# MODUL_PORTEXP_V101.net
KiCad netlist of a schematic drawn in EAGLE
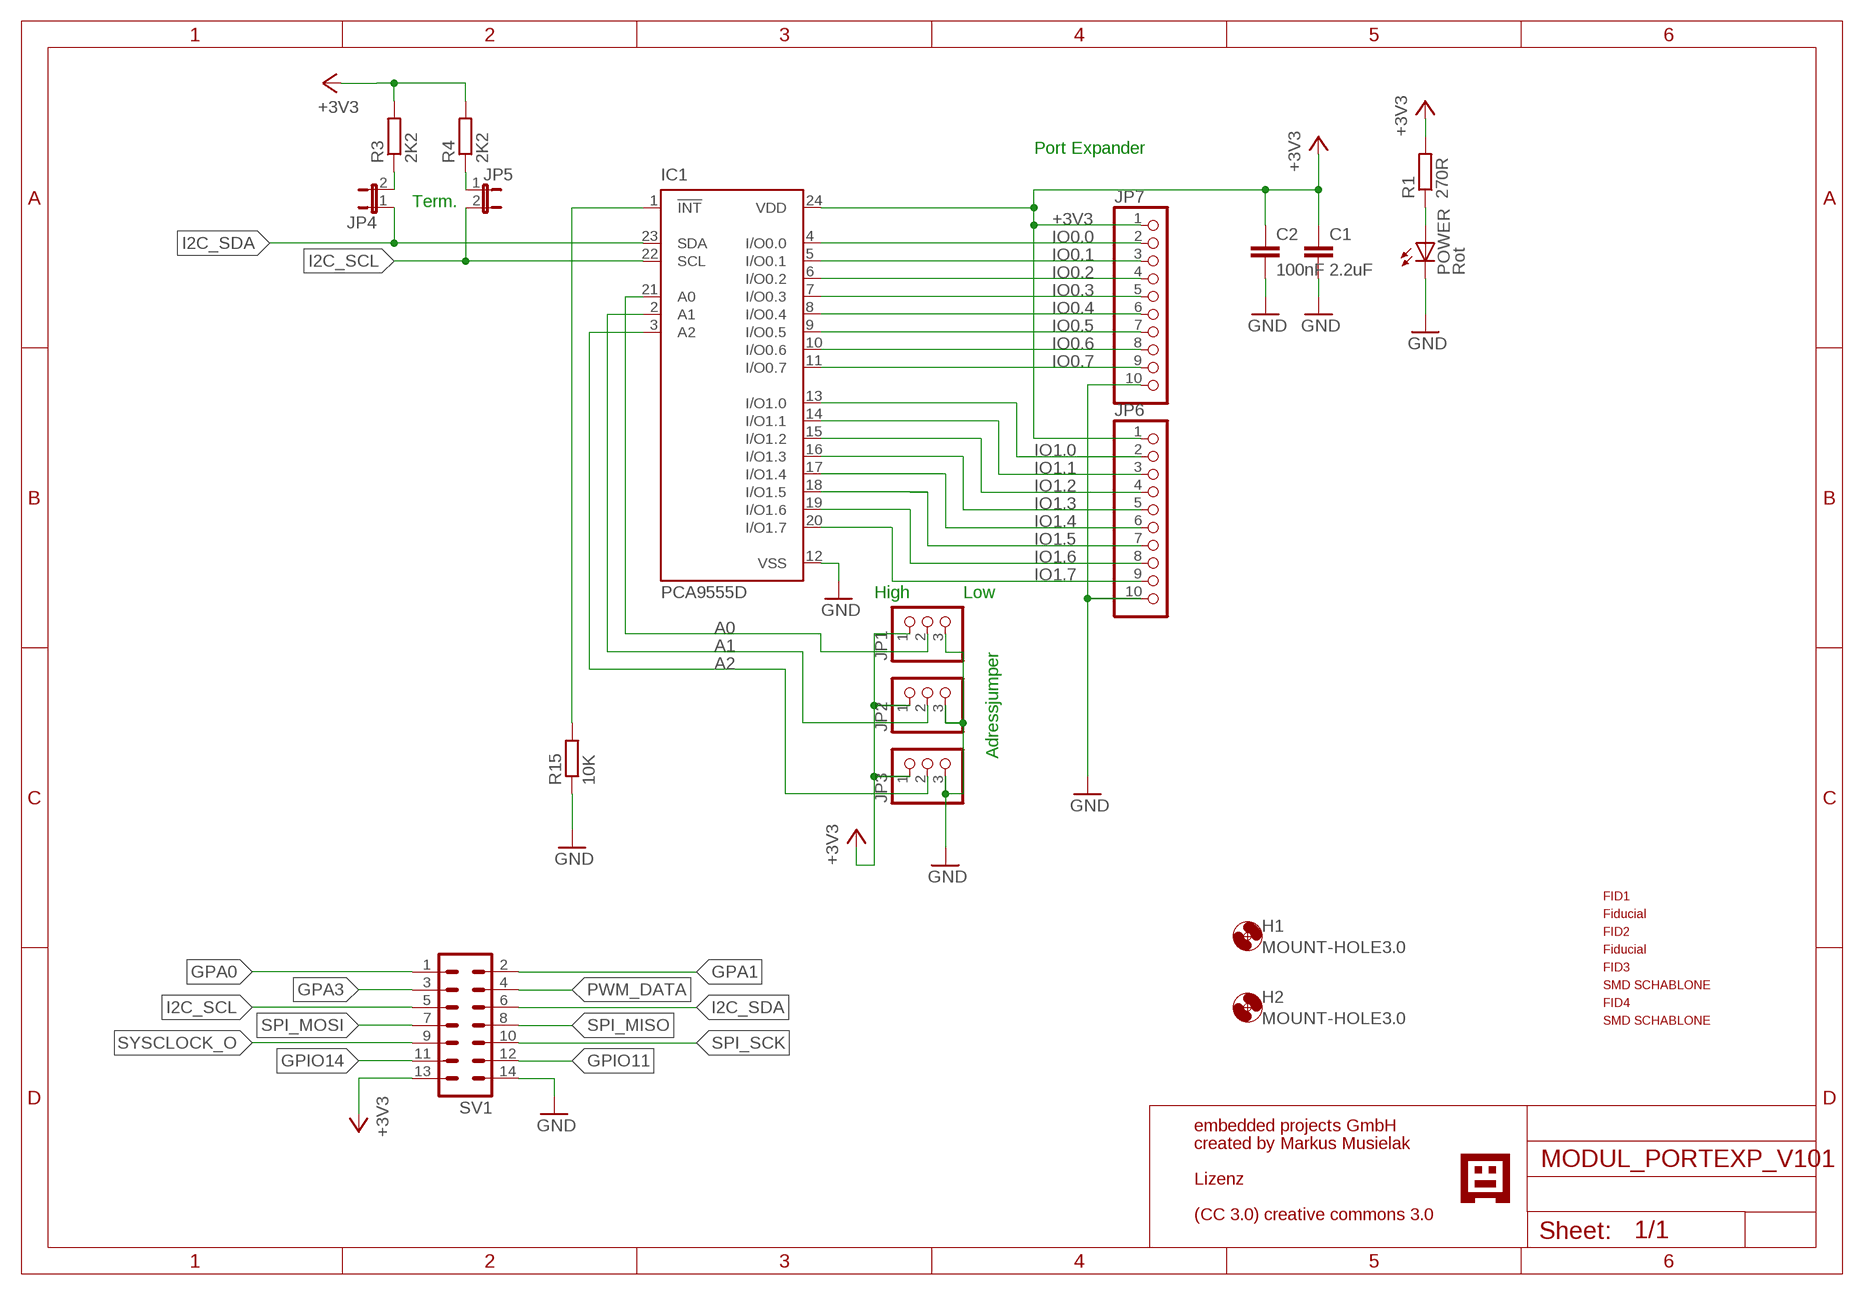
[diagram p0: schematic, sheet 1]

(export (version "E")
  (design (tool "Eeschema 10.0.6"))
  (components
    (comp (ref "C1")
      (value "2.2uF")
      (footprint "eagle-import:C0805")
      (libsource (lib "eagle-import") (part "C-EUC0805"))
    )
    (comp (ref "C2")
      (value "100nF")
      (footprint "eagle-import:C0805")
      (libsource (lib "eagle-import") (part "C-EUC0805"))
    )
    (comp (ref "FID1")
      (value "PASSERMARKEN_FIDUCIAL")
      (footprint "eagle-import:PASSERMARKEN_FIDUCIAL")
      (libsource (lib "eagle-import") (part "PASSERMARKEN_FIDUCIAL"))
    )
    (comp (ref "FID2")
      (value "PASSERMARKEN_FIDUCIAL")
      (footprint "eagle-import:PASSERMARKEN_FIDUCIAL")
      (libsource (lib "eagle-import") (part "PASSERMARKEN_FIDUCIAL"))
    )
    (comp (ref "FID3")
      (value "PASSERMARKEN_FIDUCIAL")
      (footprint "eagle-import:PASSERMARKEN_FIDUCIAL")
      (libsource (lib "eagle-import") (part "SMDSCHABLONE_PASSERMARKEN_FIDUCIAL"))
    )
    (comp (ref "FID4")
      (value "PASSERMARKEN_FIDUCIAL")
      (footprint "eagle-import:PASSERMARKEN_FIDUCIAL")
      (libsource (lib "eagle-import") (part "SMDSCHABLONE_PASSERMARKEN_FIDUCIAL"))
    )
    (comp (ref "H1")
      (value "MOUNT-HOLE3.0")
      (footprint "eagle-import:3,0")
      (libsource (lib "eagle-import") (part "MOUNT-HOLE3.0"))
    )
    (comp (ref "H2")
      (value "MOUNT-HOLE3.0")
      (footprint "eagle-import:3,0")
      (libsource (lib "eagle-import") (part "MOUNT-HOLE3.0"))
    )
    (comp (ref "IC1")
      (value "PCA9555D")
      (footprint "eagle-import:SO24")
      (fields (field (name "MPN") "PCA9555DW") (field (name "OC_FARNELL") "8906076"))
      (libsource (lib "eagle-import") (part "PCA9555D"))
    )
    (comp (ref "JP1")
      (value "PINHD-1X3")
      (footprint "eagle-import:1X03")
      (libsource (lib "eagle-import") (part "PINHD-1X3"))
    )
    (comp (ref "JP2")
      (value "PINHD-1X3")
      (footprint "eagle-import:1X03")
      (libsource (lib "eagle-import") (part "PINHD-1X3"))
    )
    (comp (ref "JP3")
      (value "PINHD-1X3")
      (footprint "eagle-import:1X03")
      (libsource (lib "eagle-import") (part "PINHD-1X3"))
    )
    (comp (ref "JP4")
      (value "JP1E")
      (footprint "eagle-import:JP1")
      (libsource (lib "eagle-import") (part "JP1E"))
    )
    (comp (ref "JP5")
      (value "JP1E")
      (footprint "eagle-import:JP1")
      (libsource (lib "eagle-import") (part "JP1E"))
    )
    (comp (ref "JP6")
      (value "PINHD-1X10")
      (footprint "eagle-import:1X10")
      (libsource (lib "eagle-import") (part "PINHD-1X10"))
    )
    (comp (ref "JP7")
      (value "PINHD-1X10")
      (footprint "eagle-import:1X10")
      (libsource (lib "eagle-import") (part "PINHD-1X10"))
    )
    (comp (ref "POWER")
      (value "Rot")
      (footprint "eagle-import:CHIP-LED0805")
      (libsource (lib "eagle-import") (part "LEDCHIP-LED0805"))
    )
    (comp (ref "R1")
      (value "270R")
      (footprint "eagle-import:R0805")
      (libsource (lib "eagle-import") (part "R-EU_R0805"))
    )
    (comp (ref "R3")
      (value "2K2")
      (footprint "eagle-import:R0805")
      (libsource (lib "eagle-import") (part "R-EU_R0805"))
    )
    (comp (ref "R4")
      (value "2K2")
      (footprint "eagle-import:R0805")
      (libsource (lib "eagle-import") (part "R-EU_R0805"))
    )
    (comp (ref "R15")
      (value "10K")
      (footprint "eagle-import:R0805")
      (libsource (lib "eagle-import") (part "R-EU_R0805"))
    )
    (comp (ref "SV1")
      (value "ML14")
      (footprint "eagle-import:ML14")
      (libsource (lib "eagle-import") (part "ML14"))
    )
    (comp (ref "U$2")
      (value "GNUBLINLOGOSIEB")
      (footprint "eagle-import:GNUSIEBDRUCK")
      (libsource (lib "eagle-import") (part "GNUBLINLOGOSIEB"))
    )
  )
  (nets
    (net (code "1") (name "+3V3") (class "Default")
      (node (ref "C1") (pin "1") (pinfunction "1_1") (pintype "passive"))
      (node (ref "C2") (pin "1") (pinfunction "1_1") (pintype "passive"))
      (node (ref "IC1") (pin "24") (pinfunction "VDD_24") (pintype "power_in"))
      (node (ref "JP1") (pin "1") (pinfunction "1_1") (pintype "passive"))
      (node (ref "JP2") (pin "1") (pinfunction "1_1") (pintype "passive"))
      (node (ref "JP3") (pin "1") (pinfunction "1_1") (pintype "passive"))
      (node (ref "JP6") (pin "1") (pinfunction "1_1") (pintype "passive"))
      (node (ref "JP7") (pin "1") (pinfunction "1_1") (pintype "passive"))
      (node (ref "R1") (pin "2") (pinfunction "2_2") (pintype "passive"))
      (node (ref "R3") (pin "2") (pinfunction "2_2") (pintype "passive"))
      (node (ref "R4") (pin "2") (pinfunction "2_2") (pintype "passive"))
      (node (ref "SV1") (pin "13") (pinfunction "13_13") (pintype "passive"))
    )
    (net (code "2") (name "/A0") (class "Default")
      (node (ref "IC1") (pin "21") (pinfunction "A0_21") (pintype "input"))
      (node (ref "JP1") (pin "2") (pinfunction "2_2") (pintype "passive"))
    )
    (net (code "3") (name "/A1") (class "Default")
      (node (ref "IC1") (pin "2") (pinfunction "A1_2") (pintype "input"))
      (node (ref "JP2") (pin "2") (pinfunction "2_2") (pintype "passive"))
    )
    (net (code "4") (name "/A2") (class "Default")
      (node (ref "IC1") (pin "3") (pinfunction "A2_3") (pintype "input"))
      (node (ref "JP3") (pin "2") (pinfunction "2_2") (pintype "passive"))
    )
    (net (code "5") (name "/IO0.0") (class "Default")
      (node (ref "IC1") (pin "4") (pinfunction "I/O0.0_4") (pintype "bidirectional"))
      (node (ref "JP7") (pin "2") (pinfunction "2_2") (pintype "passive"))
    )
    (net (code "6") (name "/IO0.1") (class "Default")
      (node (ref "IC1") (pin "5") (pinfunction "I/O0.1_5") (pintype "bidirectional"))
      (node (ref "JP7") (pin "3") (pinfunction "3_3") (pintype "passive"))
    )
    (net (code "7") (name "/IO0.2") (class "Default")
      (node (ref "IC1") (pin "6") (pinfunction "I/O0.2_6") (pintype "bidirectional"))
      (node (ref "JP7") (pin "4") (pinfunction "4_4") (pintype "passive"))
    )
    (net (code "8") (name "/IO0.3") (class "Default")
      (node (ref "IC1") (pin "7") (pinfunction "I/O0.3_7") (pintype "bidirectional"))
      (node (ref "JP7") (pin "5") (pinfunction "5_5") (pintype "passive"))
    )
    (net (code "9") (name "/IO0.4") (class "Default")
      (node (ref "IC1") (pin "8") (pinfunction "I/O0.4_8") (pintype "bidirectional"))
      (node (ref "JP7") (pin "6") (pinfunction "6_6") (pintype "passive"))
    )
    (net (code "10") (name "/IO0.5") (class "Default")
      (node (ref "IC1") (pin "9") (pinfunction "I/O0.5_9") (pintype "bidirectional"))
      (node (ref "JP7") (pin "7") (pinfunction "7_7") (pintype "passive"))
    )
    (net (code "11") (name "/IO0.6") (class "Default")
      (node (ref "IC1") (pin "10") (pinfunction "I/O0.6_10") (pintype "bidirectional"))
      (node (ref "JP7") (pin "8") (pinfunction "8_8") (pintype "passive"))
    )
    (net (code "12") (name "/IO0.7") (class "Default")
      (node (ref "IC1") (pin "11") (pinfunction "I/O0.7_11") (pintype "bidirectional"))
      (node (ref "JP7") (pin "9") (pinfunction "9_9") (pintype "passive"))
    )
    (net (code "13") (name "/IO1.0") (class "Default")
      (node (ref "IC1") (pin "13") (pinfunction "I/O1.0_13") (pintype "bidirectional"))
      (node (ref "JP6") (pin "2") (pinfunction "2_2") (pintype "passive"))
    )
    (net (code "14") (name "/IO1.1") (class "Default")
      (node (ref "IC1") (pin "14") (pinfunction "I/O1.1_14") (pintype "bidirectional"))
      (node (ref "JP6") (pin "3") (pinfunction "3_3") (pintype "passive"))
    )
    (net (code "15") (name "/IO1.2") (class "Default")
      (node (ref "IC1") (pin "15") (pinfunction "I/O1.2_15") (pintype "bidirectional"))
      (node (ref "JP6") (pin "4") (pinfunction "4_4") (pintype "passive"))
    )
    (net (code "16") (name "/IO1.3") (class "Default")
      (node (ref "IC1") (pin "16") (pinfunction "I/O1.3_16") (pintype "bidirectional"))
      (node (ref "JP6") (pin "5") (pinfunction "5_5") (pintype "passive"))
    )
    (net (code "17") (name "/IO1.4") (class "Default")
      (node (ref "IC1") (pin "17") (pinfunction "I/O1.4_17") (pintype "bidirectional"))
      (node (ref "JP6") (pin "6") (pinfunction "6_6") (pintype "passive"))
    )
    (net (code "18") (name "/IO1.5") (class "Default")
      (node (ref "IC1") (pin "18") (pinfunction "I/O1.5_18") (pintype "bidirectional"))
      (node (ref "JP6") (pin "7") (pinfunction "7_7") (pintype "passive"))
    )
    (net (code "19") (name "/IO1.6") (class "Default")
      (node (ref "IC1") (pin "19") (pinfunction "I/O1.6_19") (pintype "bidirectional"))
      (node (ref "JP6") (pin "8") (pinfunction "8_8") (pintype "passive"))
    )
    (net (code "20") (name "/IO1.7") (class "Default")
      (node (ref "IC1") (pin "20") (pinfunction "I/O1.7_20") (pintype "bidirectional"))
      (node (ref "JP6") (pin "9") (pinfunction "9_9") (pintype "passive"))
    )
    (net (code "21") (name "GND") (class "Default")
      (node (ref "C1") (pin "2") (pinfunction "2_2") (pintype "passive"))
      (node (ref "C2") (pin "2") (pinfunction "2_2") (pintype "passive"))
      (node (ref "IC1") (pin "12") (pinfunction "VSS_12") (pintype "power_in"))
      (node (ref "JP1") (pin "3") (pinfunction "3_3") (pintype "passive"))
      (node (ref "JP2") (pin "3") (pinfunction "3_3") (pintype "passive"))
      (node (ref "JP3") (pin "3") (pinfunction "3_3") (pintype "passive"))
      (node (ref "JP6") (pin "10") (pinfunction "10_10") (pintype "passive"))
      (node (ref "JP7") (pin "10") (pinfunction "10_10") (pintype "passive"))
      (node (ref "POWER") (pin "C") (pinfunction "C_C") (pintype "passive"))
      (node (ref "R15") (pin "1") (pinfunction "1_1") (pintype "passive"))
      (node (ref "SV1") (pin "14") (pinfunction "14_14") (pintype "passive"))
    )
    (net (code "22") (name "GPA0") (class "Default")
      (node (ref "SV1") (pin "1") (pinfunction "1_1") (pintype "passive"))
    )
    (net (code "23") (name "GPA1") (class "Default")
      (node (ref "SV1") (pin "2") (pinfunction "2_2") (pintype "passive"))
    )
    (net (code "24") (name "GPA3") (class "Default")
      (node (ref "SV1") (pin "3") (pinfunction "3_3") (pintype "passive"))
    )
    (net (code "25") (name "GPIO11") (class "Default")
      (node (ref "SV1") (pin "12") (pinfunction "12_12") (pintype "passive"))
    )
    (net (code "26") (name "GPIO14") (class "Default")
      (node (ref "SV1") (pin "11") (pinfunction "11_11") (pintype "passive"))
    )
    (net (code "27") (name "I2C_SCL") (class "Default")
      (node (ref "IC1") (pin "22") (pinfunction "SCL_22") (pintype "input"))
      (node (ref "JP5") (pin "2") (pinfunction "2_2") (pintype "passive"))
      (node (ref "SV1") (pin "5") (pinfunction "5_5") (pintype "passive"))
    )
    (net (code "28") (name "I2C_SDA") (class "Default")
      (node (ref "IC1") (pin "23") (pinfunction "SDA_23") (pintype "bidirectional"))
      (node (ref "JP4") (pin "1") (pinfunction "1_1") (pintype "passive"))
      (node (ref "SV1") (pin "6") (pinfunction "6_6") (pintype "passive"))
    )
    (net (code "29") (name "Net-(IC1-~{INT})") (class "Default")
      (node (ref "IC1") (pin "1") (pinfunction "~{INT}_1") (pintype "output"))
      (node (ref "R15") (pin "2") (pinfunction "2_2") (pintype "passive"))
    )
    (net (code "30") (name "Net-(JP4-Pad2)") (class "Default")
      (node (ref "JP4") (pin "2") (pinfunction "2_2") (pintype "passive"))
      (node (ref "R3") (pin "1") (pinfunction "1_1") (pintype "passive"))
    )
    (net (code "31") (name "Net-(JP5-Pad1)") (class "Default")
      (node (ref "JP5") (pin "1") (pinfunction "1_1") (pintype "passive"))
      (node (ref "R4") (pin "1") (pinfunction "1_1") (pintype "passive"))
    )
    (net (code "32") (name "Net-(POWER-PadA)") (class "Default")
      (node (ref "POWER") (pin "A") (pinfunction "A_A") (pintype "passive"))
      (node (ref "R1") (pin "1") (pinfunction "1_1") (pintype "passive"))
    )
    (net (code "33") (name "PWM_DATA") (class "Default")
      (node (ref "SV1") (pin "4") (pinfunction "4_4") (pintype "passive"))
    )
    (net (code "34") (name "SPI_MISO") (class "Default")
      (node (ref "SV1") (pin "8") (pinfunction "8_8") (pintype "passive"))
    )
    (net (code "35") (name "SPI_MOSI") (class "Default")
      (node (ref "SV1") (pin "7") (pinfunction "7_7") (pintype "passive"))
    )
    (net (code "36") (name "SPI_SCK") (class "Default")
      (node (ref "SV1") (pin "10") (pinfunction "10_10") (pintype "passive"))
    )
    (net (code "37") (name "SYSCLOCK_O") (class "Default")
      (node (ref "SV1") (pin "9") (pinfunction "9_9") (pintype "passive"))
    )
  )
)
